# 3V3_StepDown.net
KiCad netlist of a schematic drawn in Altium Designer
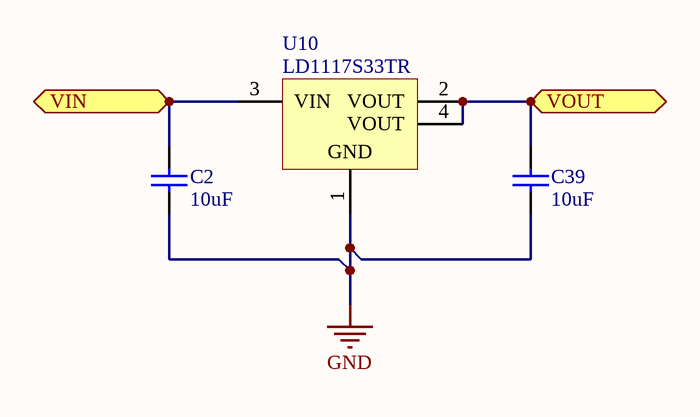
[diagram p0: 3V3_StepDown.SchDoc]

(export (version "E")
  (design (tool "Eeschema 10.0.6"))
  (components
    (comp (ref "C2")
      (value "10uF")
      (footprint "CAPC0603(1608)100_L")
      (description "CAP 10uF 6.3V ±20% 0603 (1608 Metric) Thickness 1mm SMD")
      (fields (field (name "TOLERANCE") "Â±20%"))
      (libsource (lib "Altium Content Vault") (part "CMP-1035-02797-1"))
    )
    (comp (ref "C39")
      (value "10uF")
      (footprint "CAPC0603(1608)100_L")
      (description "CAP 10uF 6.3V ±20% 0603 (1608 Metric) Thickness 1mm SMD")
      (fields (field (name "TOLERANCE") "Â±20%"))
      (libsource (lib "Altium Content Vault") (part "CMP-1035-02797-1"))
    )
    (comp (ref "U10")
      (value "LD1117S33TR")
      (footprint "SOT-223_L")
      (description "Fixed Low Drop Positive Voltage Regulator, 3.3V, 4-Pin SOT-223, Tape and Reel")
      (libsource (lib "Altium Content Vault") (part "PM-REG-LD1117-SOT4"))
    )
  )
  (nets
    (net (code "1") (name "/VIN") (class "Default")
      (node (ref "C2") (pin "2") (pinfunction "2_2") (pintype "passive"))
      (node (ref "U10") (pin "3") (pinfunction "VIN_3") (pintype "power_in"))
    )
    (net (code "2") (name "/VOUT") (class "Default")
      (node (ref "C39") (pin "2") (pinfunction "2_2") (pintype "passive"))
      (node (ref "U10") (pin "2") (pinfunction "VOUT_2") (pintype "power_in"))
      (node (ref "U10") (pin "4") (pinfunction "VOUT_4") (pintype "power_in"))
    )
    (net (code "3") (name "GND") (class "Default")
      (node (ref "C2") (pin "1") (pinfunction "1_1") (pintype "passive"))
      (node (ref "C39") (pin "1") (pinfunction "1_1") (pintype "passive"))
      (node (ref "U10") (pin "1") (pinfunction "GND_1") (pintype "power_in"))
    )
  )
)
